# Sheet2.net
KiCad netlist of a schematic drawn in Altium Designer
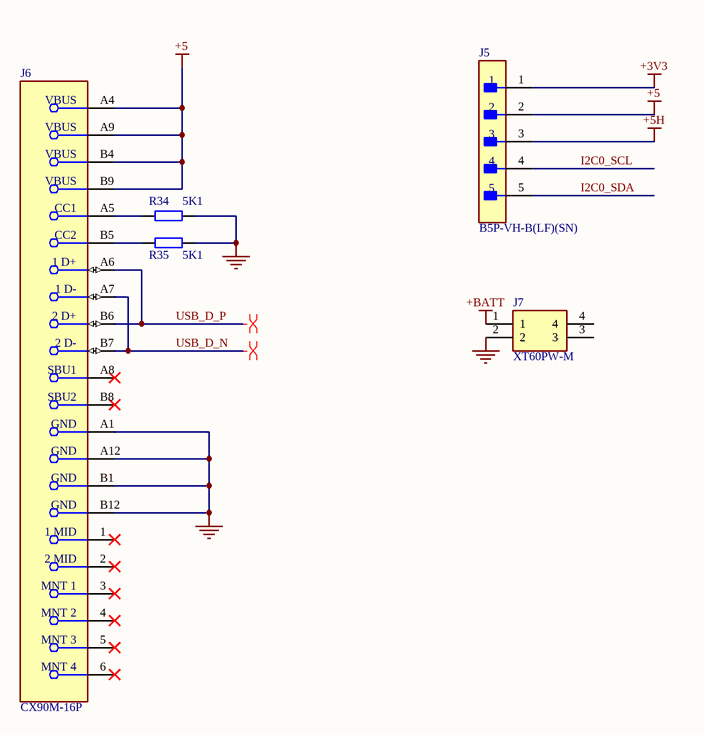
[diagram p0: Sheet2.SchDoc]

(export (version "E")
  (design (tool "Eeschema 10.0.6"))
  (components
    (comp (ref "J5")
      (value "B5P-VH-B(LF)(SN)")
      (footprint "FP-B5P-VH-B_LF_SN-MFG")
      (description "CONN HEADER VERT 5POS 3.96MM")
      (libsource (lib "Altium Content Vault") (part "bf93c07fd2649a848d0ec8585582aab"))
    )
    (comp (ref "J6")
      (value "CX90M-16P")
      (footprint "FP-CX90M-16P-MFG")
      (description "CONN RCPT USB2.0 TYPEC 16POS SMD")
      (libsource (lib "Altium Content Vault") (part "6b7e9819a715c2d1d3babe584a73dea"))
    )
    (comp (ref "J7")
      (value "XT60PW-M")
      (footprint "SamacSys:XT60PWM")
      (description "Connector")
      (libsource (lib "SamacSys") (part "XT60PW-M"))
    )
    (comp (ref "R34")
      (value "5K1")
      (footprint "RES_0402")
      (description "Resistor SMD 0402")
      (libsource (lib "SchematicSchlib1") (part "RES_0402"))
    )
    (comp (ref "R35")
      (value "5K1")
      (footprint "RES_0402")
      (description "Resistor SMD 0402")
      (libsource (lib "SchematicSchlib1") (part "RES_0402"))
    )
  )
  (nets
    (net (code "1") (name "+3V3") (class "Default")
      (node (ref "J5") (pin "1") (pinfunction "1_1") (pintype "passive"))
    )
    (net (code "2") (name "+5") (class "Default")
      (node (ref "J5") (pin "2") (pinfunction "2_2") (pintype "passive"))
      (node (ref "J6") (pin "A4") (pinfunction "VBUS_A4") (pintype "power_in"))
      (node (ref "J6") (pin "A9") (pinfunction "VBUS_A9") (pintype "power_in"))
      (node (ref "J6") (pin "B4") (pinfunction "VBUS_B4") (pintype "power_in"))
      (node (ref "J6") (pin "B9") (pinfunction "VBUS_B9") (pintype "power_in"))
    )
    (net (code "3") (name "+5H") (class "Default")
      (node (ref "J5") (pin "3") (pinfunction "3_3") (pintype "passive"))
    )
    (net (code "4") (name "+BATT") (class "Default")
      (node (ref "J7") (pin "1") (pinfunction "1_1") (pintype "passive"))
    )
    (net (code "5") (name "/I2C0_SCL") (class "Default")
      (node (ref "J5") (pin "4") (pinfunction "4_4") (pintype "passive"))
    )
    (net (code "6") (name "/I2C0_SDA") (class "Default")
      (node (ref "J5") (pin "5") (pinfunction "5_5") (pintype "passive"))
    )
    (net (code "7") (name "/USB_D_N") (class "Default")
      (node (ref "J6") (pin "A7") (pinfunction "1_D-_A7") (pintype "bidirectional"))
      (node (ref "J6") (pin "B7") (pinfunction "2_D-_B7") (pintype "bidirectional"))
    )
    (net (code "8") (name "/USB_D_P") (class "Default")
      (node (ref "J6") (pin "A6") (pinfunction "1_D+_A6") (pintype "bidirectional"))
      (node (ref "J6") (pin "B6") (pinfunction "2_D+_B6") (pintype "bidirectional"))
    )
    (net (code "9") (name "GND") (class "Default")
      (node (ref "J6") (pin "A1") (pinfunction "GND_A1") (pintype "power_in"))
      (node (ref "J6") (pin "A12") (pinfunction "GND_A12") (pintype "power_in"))
      (node (ref "J6") (pin "B1") (pinfunction "GND_B1") (pintype "power_in"))
      (node (ref "J6") (pin "B12") (pinfunction "GND_B12") (pintype "power_in"))
      (node (ref "J7") (pin "2") (pinfunction "2_2") (pintype "passive"))
      (node (ref "R34") (pin "2") (pinfunction "2_2") (pintype "passive"))
      (node (ref "R35") (pin "2") (pinfunction "2_2") (pintype "passive"))
    )
    (net (code "10") (name "Net-(J6-CC1)") (class "Default")
      (node (ref "J6") (pin "A5") (pinfunction "CC1_A5") (pintype "passive"))
      (node (ref "R34") (pin "1") (pinfunction "1_1") (pintype "passive"))
    )
    (net (code "11") (name "Net-(J6-CC2)") (class "Default")
      (node (ref "J6") (pin "B5") (pinfunction "CC2_B5") (pintype "passive"))
      (node (ref "R35") (pin "1") (pinfunction "1_1") (pintype "passive"))
    )
    (net (code "12") (name "unconnected-(J6-1_MID-Pad1)") (class "Default")
      (node (ref "J6") (pin "1") (pinfunction "1_MID_1") (pintype "passive+no_connect"))
    )
    (net (code "13") (name "unconnected-(J6-2_MID-Pad2)") (class "Default")
      (node (ref "J6") (pin "2") (pinfunction "2_MID_2") (pintype "passive+no_connect"))
    )
    (net (code "14") (name "unconnected-(J6-MNT_1-Pad3)") (class "Default")
      (node (ref "J6") (pin "3") (pinfunction "MNT_1_3") (pintype "passive+no_connect"))
    )
    (net (code "15") (name "unconnected-(J6-MNT_2-Pad4)") (class "Default")
      (node (ref "J6") (pin "4") (pinfunction "MNT_2_4") (pintype "passive+no_connect"))
    )
    (net (code "16") (name "unconnected-(J6-MNT_3-Pad5)") (class "Default")
      (node (ref "J6") (pin "5") (pinfunction "MNT_3_5") (pintype "passive+no_connect"))
    )
    (net (code "17") (name "unconnected-(J6-MNT_4-Pad6)") (class "Default")
      (node (ref "J6") (pin "6") (pinfunction "MNT_4_6") (pintype "passive+no_connect"))
    )
    (net (code "18") (name "unconnected-(J6-SBU1-PadA8)") (class "Default")
      (node (ref "J6") (pin "A8") (pinfunction "SBU1_A8") (pintype "passive+no_connect"))
    )
    (net (code "19") (name "unconnected-(J6-SBU2-PadB8)") (class "Default")
      (node (ref "J6") (pin "B8") (pinfunction "SBU2_B8") (pintype "passive+no_connect"))
    )
    (net (code "20") (name "unconnected-(J7-Pad3)") (class "Default")
      (node (ref "J7") (pin "3") (pinfunction "3_3") (pintype "passive"))
    )
    (net (code "21") (name "unconnected-(J7-Pad4)") (class "Default")
      (node (ref "J7") (pin "4") (pinfunction "4_4") (pintype "passive"))
    )
  )
)
